# Schaltplan.net
KiCad netlist of a schematic drawn in EAGLE
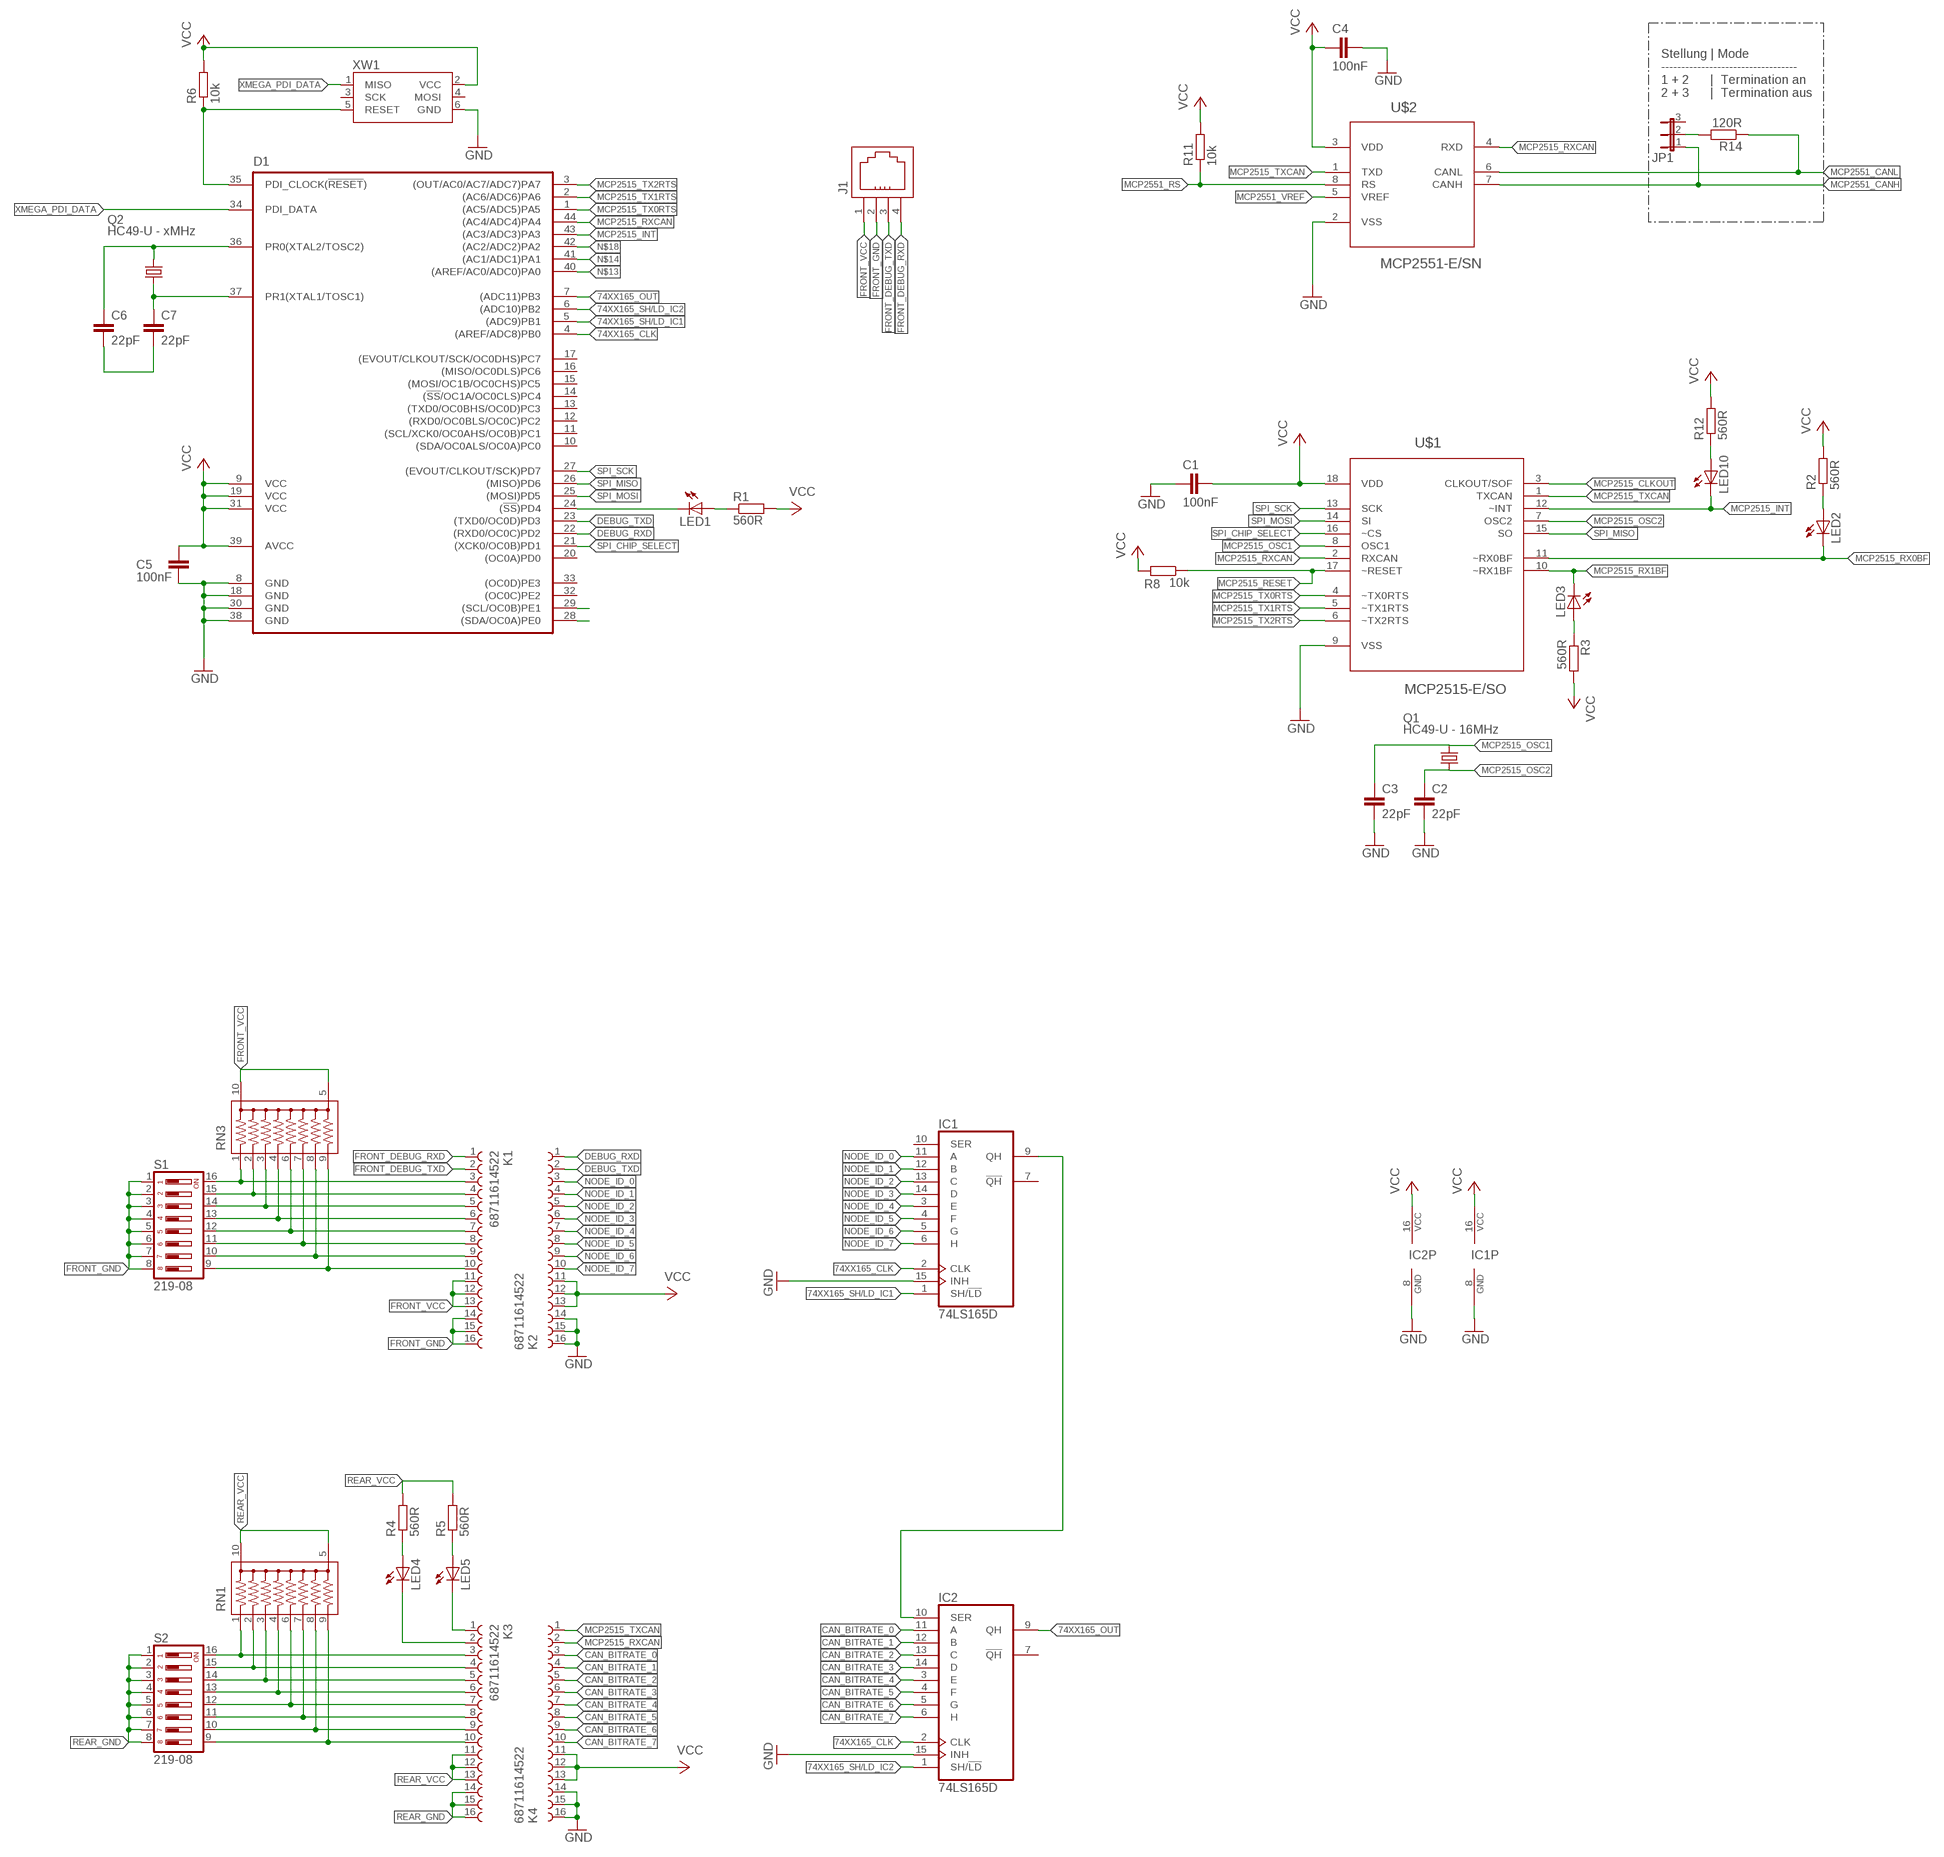
[diagram p0: schematic, sheet 1]

(export (version "E")
  (design (tool "Eeschema 10.0.6"))
  (components
    (comp (ref "C1")
      (value "100nF")
      (footprint "eagle-import:C1206")
      (libsource (lib "eagle-import") (part "C-EUC1206"))
    )
    (comp (ref "C2")
      (value "22pF")
      (footprint "eagle-import:C1206")
      (libsource (lib "eagle-import") (part "C-EUC1206"))
    )
    (comp (ref "C3")
      (value "22pF")
      (footprint "eagle-import:C1206")
      (libsource (lib "eagle-import") (part "C-EUC1206"))
    )
    (comp (ref "C4")
      (value "100nF")
      (footprint "eagle-import:C1206")
      (libsource (lib "eagle-import") (part "C-EUC1206"))
    )
    (comp (ref "C5")
      (value "100nF")
      (footprint "eagle-import:C1206")
      (libsource (lib "eagle-import") (part "C-EUC1206"))
    )
    (comp (ref "C6")
      (value "22pF")
      (footprint "eagle-import:C1206")
      (libsource (lib "eagle-import") (part "C-EUC1206"))
    )
    (comp (ref "C7")
      (value "22pF")
      (footprint "eagle-import:C1206")
      (libsource (lib "eagle-import") (part "C-EUC1206"))
    )
    (comp (ref "D1")
      (value "ATXMEGA16D4/32D4/64D4/128D4-A")
      (footprint "eagle-import:TQFP44A")
      (libsource (lib "eagle-import") (part "ATXMEGA16D4/32D4/64D4/128D4-A"))
    )
    (comp (ref "IC1")
      (value "74LS165D")
      (footprint "eagle-import:SO16")
      (libsource (lib "eagle-import") (part "74165DLS"))
    )
    (comp (ref "IC2")
      (value "74LS165D")
      (footprint "eagle-import:SO16")
      (libsource (lib "eagle-import") (part "74165DLS"))
    )
    (comp (ref "J1")
      (value "615004143821")
      (footprint "eagle-import:615004143821")
      (libsource (lib "eagle-import") (part "615004143821"))
    )
    (comp (ref "JP1")
      (value "JP2E")
      (footprint "eagle-import:JP2")
      (libsource (lib "eagle-import") (part "JP2E"))
    )
    (comp (ref "K1")
      (value "68711614522")
      (footprint "eagle-import:68711614522")
      (libsource (lib "eagle-import") (part "68711614522"))
    )
    (comp (ref "K2")
      (value "68711614522")
      (footprint "eagle-import:68711614522")
      (libsource (lib "eagle-import") (part "68711614522"))
    )
    (comp (ref "K3")
      (value "68711614522")
      (footprint "eagle-import:68711614522")
      (libsource (lib "eagle-import") (part "68711614522"))
    )
    (comp (ref "K4")
      (value "68711614522")
      (footprint "eagle-import:68711614522")
      (libsource (lib "eagle-import") (part "68711614522"))
    )
    (comp (ref "LED1")
      (value "LEDSML1206")
      (footprint "eagle-import:SML1206")
      (libsource (lib "eagle-import") (part "LEDSML1206"))
    )
    (comp (ref "LED2")
      (value "LEDSML1206")
      (footprint "eagle-import:SML1206")
      (libsource (lib "eagle-import") (part "LEDSML1206"))
    )
    (comp (ref "LED3")
      (value "LEDSML1206")
      (footprint "eagle-import:SML1206")
      (libsource (lib "eagle-import") (part "LEDSML1206"))
    )
    (comp (ref "LED4")
      (value "LEDSML1206")
      (footprint "eagle-import:SML1206")
      (libsource (lib "eagle-import") (part "LEDSML1206"))
    )
    (comp (ref "LED5")
      (value "LEDSML1206")
      (footprint "eagle-import:SML1206")
      (libsource (lib "eagle-import") (part "LEDSML1206"))
    )
    (comp (ref "LED10")
      (value "LEDSML1206")
      (footprint "eagle-import:SML1206")
      (libsource (lib "eagle-import") (part "LEDSML1206"))
    )
    (comp (ref "Q1")
      (value "HC49-U - 16MHz")
      (footprint "eagle-import:HC49")
      (libsource (lib "eagle-import") (part "HC49-U"))
    )
    (comp (ref "Q2")
      (value "HC49-U - xMHz")
      (footprint "eagle-import:HC49")
      (libsource (lib "eagle-import") (part "HC49-U"))
    )
    (comp (ref "R1")
      (value "560R")
      (footprint "eagle-import:R1206")
      (libsource (lib "eagle-import") (part "R-EU_R1206"))
    )
    (comp (ref "R2")
      (value "560R")
      (footprint "eagle-import:R1206")
      (libsource (lib "eagle-import") (part "R-EU_R1206"))
    )
    (comp (ref "R3")
      (value "560R")
      (footprint "eagle-import:R1206")
      (libsource (lib "eagle-import") (part "R-EU_R1206"))
    )
    (comp (ref "R4")
      (value "560R")
      (footprint "eagle-import:R1206")
      (libsource (lib "eagle-import") (part "R-EU_R1206"))
    )
    (comp (ref "R5")
      (value "560R")
      (footprint "eagle-import:R1206")
      (libsource (lib "eagle-import") (part "R-EU_R1206"))
    )
    (comp (ref "R6")
      (value "10k")
      (footprint "eagle-import:R1206")
      (libsource (lib "eagle-import") (part "R-EU_R1206"))
    )
    (comp (ref "R8")
      (value "10k")
      (footprint "eagle-import:R1206")
      (libsource (lib "eagle-import") (part "R-EU_R1206"))
    )
    (comp (ref "R11")
      (value "10k")
      (footprint "eagle-import:R1206")
      (libsource (lib "eagle-import") (part "R-EU_R1206"))
    )
    (comp (ref "R12")
      (value "560R")
      (footprint "eagle-import:R1206")
      (libsource (lib "eagle-import") (part "R-EU_R1206"))
    )
    (comp (ref "R14")
      (value "120R")
      (footprint "eagle-import:R1206")
      (libsource (lib "eagle-import") (part "R-EU_R1206"))
    )
    (comp (ref "RN1")
      (value "745-10")
      (footprint "eagle-import:745-10")
      (libsource (lib "eagle-import") (part "745-10"))
    )
    (comp (ref "RN3")
      (value "745-10")
      (footprint "eagle-import:745-10")
      (libsource (lib "eagle-import") (part "745-10"))
    )
    (comp (ref "S1")
      (value "219-08")
      (footprint "eagle-import:CTS-219-08")
      (libsource (lib "eagle-import") (part "219-08"))
    )
    (comp (ref "S2")
      (value "219-08")
      (footprint "eagle-import:CTS-219-08")
      (libsource (lib "eagle-import") (part "219-08"))
    )
    (comp (ref "U$1")
      (value "MCP2515-E/SO")
      (footprint "eagle-import:SOIC127P1030X265-18N")
      (libsource (lib "eagle-import") (part "MCP2515-E/SO"))
    )
    (comp (ref "U$2")
      (value "MCP2551-E/SN")
      (footprint "eagle-import:SOIC127P600X175-8N")
      (libsource (lib "eagle-import") (part "MCP2551-E/SN"))
    )
    (comp (ref "XW1")
      (value "WSL6")
      (footprint "eagle-import:WSL")
      (libsource (lib "eagle-import") (part "WSL6"))
    )
  )
  (nets
    (net (code "1") (name "74XX165_CLK") (class "Default")
      (node (ref "D1") (pin "4") (pinfunction "(AREF/ADC8)PB0_4") (pintype "bidirectional"))
      (node (ref "IC1") (pin "2") (pinfunction "CLK_2") (pintype "input"))
      (node (ref "IC2") (pin "2") (pinfunction "CLK_2") (pintype "input"))
    )
    (net (code "2") (name "74XX165_OUT") (class "Default")
      (node (ref "D1") (pin "7") (pinfunction "(ADC11)PB3_7") (pintype "bidirectional"))
      (node (ref "IC2") (pin "9") (pinfunction "QH_9") (pintype "output"))
    )
    (net (code "3") (name "74XX165_SH{slash}LD_IC1") (class "Default")
      (node (ref "D1") (pin "5") (pinfunction "(ADC9)PB1_5") (pintype "bidirectional"))
      (node (ref "IC1") (pin "1") (pinfunction "SH/~{LD}_1") (pintype "input"))
    )
    (net (code "4") (name "74XX165_SH{slash}LD_IC2") (class "Default")
      (node (ref "D1") (pin "6") (pinfunction "(ADC10)PB2_6") (pintype "bidirectional"))
      (node (ref "IC2") (pin "1") (pinfunction "SH/~{LD}_1") (pintype "input"))
    )
    (net (code "5") (name "CAN_BITRATE_0") (class "Default")
      (node (ref "IC2") (pin "11") (pinfunction "A_11") (pintype "input"))
      (node (ref "K4") (pin "3") (pinfunction "3_3") (pintype "passive"))
    )
    (net (code "6") (name "CAN_BITRATE_1") (class "Default")
      (node (ref "IC2") (pin "12") (pinfunction "B_12") (pintype "input"))
      (node (ref "K4") (pin "4") (pinfunction "4_4") (pintype "passive"))
    )
    (net (code "7") (name "CAN_BITRATE_2") (class "Default")
      (node (ref "IC2") (pin "13") (pinfunction "C_13") (pintype "input"))
      (node (ref "K4") (pin "5") (pinfunction "5_5") (pintype "passive"))
    )
    (net (code "8") (name "CAN_BITRATE_3") (class "Default")
      (node (ref "IC2") (pin "14") (pinfunction "D_14") (pintype "input"))
      (node (ref "K4") (pin "6") (pinfunction "6_6") (pintype "passive"))
    )
    (net (code "9") (name "CAN_BITRATE_4") (class "Default")
      (node (ref "IC2") (pin "3") (pinfunction "E_3") (pintype "input"))
      (node (ref "K4") (pin "7") (pinfunction "7_7") (pintype "passive"))
    )
    (net (code "10") (name "CAN_BITRATE_5") (class "Default")
      (node (ref "IC2") (pin "4") (pinfunction "F_4") (pintype "input"))
      (node (ref "K4") (pin "8") (pinfunction "8_8") (pintype "passive"))
    )
    (net (code "11") (name "CAN_BITRATE_6") (class "Default")
      (node (ref "IC2") (pin "5") (pinfunction "G_5") (pintype "input"))
      (node (ref "K4") (pin "9") (pinfunction "9_9") (pintype "passive"))
    )
    (net (code "12") (name "CAN_BITRATE_7") (class "Default")
      (node (ref "IC2") (pin "6") (pinfunction "H_6") (pintype "input"))
      (node (ref "K4") (pin "10") (pinfunction "10_10") (pintype "passive"))
    )
    (net (code "13") (name "DEBUG_RXD") (class "Default")
      (node (ref "D1") (pin "22") (pinfunction "(RXD0/OC0C)PD2_22") (pintype "bidirectional"))
      (node (ref "K2") (pin "1") (pinfunction "1_1") (pintype "passive"))
    )
    (net (code "14") (name "DEBUG_TXD") (class "Default")
      (node (ref "D1") (pin "23") (pinfunction "(TXD0/OC0D)PD3_23") (pintype "bidirectional"))
      (node (ref "K2") (pin "2") (pinfunction "2_2") (pintype "passive"))
    )
    (net (code "15") (name "FRONT_DEBUG_RXD") (class "Default")
      (node (ref "J1") (pin "4") (pinfunction "1_4") (pintype "passive"))
      (node (ref "K1") (pin "1") (pinfunction "1_1") (pintype "passive"))
    )
    (net (code "16") (name "FRONT_DEBUG_TXD") (class "Default")
      (node (ref "J1") (pin "3") (pinfunction "2_3") (pintype "passive"))
      (node (ref "K1") (pin "2") (pinfunction "2_2") (pintype "passive"))
    )
    (net (code "17") (name "FRONT_GND") (class "Default")
      (node (ref "J1") (pin "2") (pinfunction "3_2") (pintype "passive"))
      (node (ref "K1") (pin "14") (pinfunction "14_14") (pintype "passive"))
      (node (ref "K1") (pin "15") (pinfunction "15_15") (pintype "passive"))
      (node (ref "K1") (pin "16") (pinfunction "16_16") (pintype "passive"))
      (node (ref "S1") (pin "1") (pinfunction "1_1") (pintype "passive"))
      (node (ref "S1") (pin "2") (pinfunction "2_2") (pintype "passive"))
      (node (ref "S1") (pin "3") (pinfunction "3_3") (pintype "passive"))
      (node (ref "S1") (pin "4") (pinfunction "4_4") (pintype "passive"))
      (node (ref "S1") (pin "5") (pinfunction "5_5") (pintype "passive"))
      (node (ref "S1") (pin "6") (pinfunction "6_6") (pintype "passive"))
      (node (ref "S1") (pin "7") (pinfunction "7_7") (pintype "passive"))
      (node (ref "S1") (pin "8") (pinfunction "8_8") (pintype "passive"))
    )
    (net (code "18") (name "FRONT_VCC") (class "Default")
      (node (ref "J1") (pin "1") (pinfunction "4_1") (pintype "passive"))
      (node (ref "K1") (pin "11") (pinfunction "11_11") (pintype "passive"))
      (node (ref "K1") (pin "12") (pinfunction "12_12") (pintype "passive"))
      (node (ref "K1") (pin "13") (pinfunction "13_13") (pintype "passive"))
      (node (ref "RN3") (pin "10") (pinfunction "10_10") (pintype "passive"))
      (node (ref "RN3") (pin "5") (pinfunction "5_5") (pintype "passive"))
    )
    (net (code "19") (name "GND") (class "Default")
      (node (ref "C1") (pin "2") (pinfunction "2_2") (pintype "passive"))
      (node (ref "C2") (pin "2") (pinfunction "2_2") (pintype "passive"))
      (node (ref "C3") (pin "2") (pinfunction "2_2") (pintype "passive"))
      (node (ref "C4") (pin "1") (pinfunction "1_1") (pintype "passive"))
      (node (ref "C5") (pin "2") (pinfunction "2_2") (pintype "passive"))
      (node (ref "D1") (pin "18") (pinfunction "GND_18") (pintype "power_in"))
      (node (ref "D1") (pin "30") (pinfunction "GND_30") (pintype "power_in"))
      (node (ref "D1") (pin "38") (pinfunction "GND_38") (pintype "power_in"))
      (node (ref "D1") (pin "8") (pinfunction "GND_8") (pintype "power_in"))
      (node (ref "IC1") (pin "15") (pinfunction "INH_15") (pintype "input"))
      (node (ref "IC1") (pin "8") (pinfunction "GND_8") (pintype "power_in"))
      (node (ref "IC2") (pin "15") (pinfunction "INH_15") (pintype "input"))
      (node (ref "IC2") (pin "8") (pinfunction "GND_8") (pintype "power_in"))
      (node (ref "K2") (pin "14") (pinfunction "14_14") (pintype "passive"))
      (node (ref "K2") (pin "15") (pinfunction "15_15") (pintype "passive"))
      (node (ref "K2") (pin "16") (pinfunction "16_16") (pintype "passive"))
      (node (ref "K4") (pin "14") (pinfunction "14_14") (pintype "passive"))
      (node (ref "K4") (pin "15") (pinfunction "15_15") (pintype "passive"))
      (node (ref "K4") (pin "16") (pinfunction "16_16") (pintype "passive"))
      (node (ref "U$1") (pin "9") (pinfunction "VSS_9") (pintype "power_in"))
      (node (ref "U$2") (pin "2") (pinfunction "VSS_2") (pintype "power_in"))
      (node (ref "XW1") (pin "6") (pinfunction "GND_6") (pintype "power_in"))
    )
    (net (code "20") (name "MCP2515_CLKOUT") (class "Default")
      (node (ref "U$1") (pin "3") (pinfunction "CLKOUT/SOF_3") (pintype "output"))
    )
    (net (code "21") (name "MCP2515_INT") (class "Default")
      (node (ref "D1") (pin "43") (pinfunction "(AC3/ADC3)PA3_43") (pintype "bidirectional"))
      (node (ref "LED10") (pin "C") (pinfunction "C_C") (pintype "passive"))
      (node (ref "U$1") (pin "12") (pinfunction "~{INT}_12") (pintype "output"))
    )
    (net (code "22") (name "MCP2515_OSC1") (class "Default")
      (node (ref "C3") (pin "1") (pinfunction "1_1") (pintype "passive"))
      (node (ref "Q1") (pin "2") (pinfunction "2_2") (pintype "passive"))
      (node (ref "U$1") (pin "8") (pinfunction "OSC1_8") (pintype "input"))
    )
    (net (code "23") (name "MCP2515_OSC2") (class "Default")
      (node (ref "C2") (pin "1") (pinfunction "1_1") (pintype "passive"))
      (node (ref "Q1") (pin "1") (pinfunction "1_1") (pintype "passive"))
      (node (ref "U$1") (pin "7") (pinfunction "OSC2_7") (pintype "output"))
    )
    (net (code "24") (name "MCP2515_RESET") (class "Default")
      (node (ref "R8") (pin "1") (pinfunction "1_1") (pintype "passive"))
      (node (ref "U$1") (pin "17") (pinfunction "~{RESET}_17") (pintype "input"))
    )
    (net (code "25") (name "MCP2515_RX0BF") (class "Default")
      (node (ref "LED2") (pin "C") (pinfunction "C_C") (pintype "passive"))
      (node (ref "U$1") (pin "11") (pinfunction "~{RX0BF}_11") (pintype "output"))
    )
    (net (code "26") (name "MCP2515_RX1BF") (class "Default")
      (node (ref "LED3") (pin "C") (pinfunction "C_C") (pintype "passive"))
      (node (ref "U$1") (pin "10") (pinfunction "~{RX1BF}_10") (pintype "output"))
    )
    (net (code "27") (name "MCP2515_RXCAN") (class "Default")
      (node (ref "D1") (pin "44") (pinfunction "(AC4/ADC4)PA4_44") (pintype "bidirectional"))
      (node (ref "K4") (pin "2") (pinfunction "2_2") (pintype "passive"))
      (node (ref "U$1") (pin "2") (pinfunction "RXCAN_2") (pintype "input"))
      (node (ref "U$2") (pin "4") (pinfunction "RXD_4") (pintype "output"))
    )
    (net (code "28") (name "MCP2515_TX0RTS") (class "Default")
      (node (ref "D1") (pin "1") (pinfunction "(AC5/ADC5)PA5_1") (pintype "bidirectional"))
      (node (ref "U$1") (pin "4") (pinfunction "~{TX0RTS}_4") (pintype "input"))
    )
    (net (code "29") (name "MCP2515_TX1RTS") (class "Default")
      (node (ref "D1") (pin "2") (pinfunction "(AC6/ADC6)PA6_2") (pintype "bidirectional"))
      (node (ref "U$1") (pin "5") (pinfunction "~{TX1RTS}_5") (pintype "input"))
    )
    (net (code "30") (name "MCP2515_TX2RTS") (class "Default")
      (node (ref "D1") (pin "3") (pinfunction "(OUT/AC0/AC7/ADC7)PA7_3") (pintype "bidirectional"))
      (node (ref "U$1") (pin "6") (pinfunction "~{TX2RTS}_6") (pintype "input"))
    )
    (net (code "31") (name "MCP2515_TXCAN") (class "Default")
      (node (ref "K4") (pin "1") (pinfunction "1_1") (pintype "passive"))
      (node (ref "U$1") (pin "1") (pinfunction "TXCAN_1") (pintype "output"))
      (node (ref "U$2") (pin "1") (pinfunction "TXD_1") (pintype "input"))
    )
    (net (code "32") (name "MCP2551_CANH") (class "Default")
      (node (ref "JP1") (pin "1") (pinfunction "1_1") (pintype "passive"))
      (node (ref "U$2") (pin "7") (pinfunction "CANH_7") (pintype "output"))
    )
    (net (code "33") (name "MCP2551_CANL") (class "Default")
      (node (ref "R14") (pin "1") (pinfunction "1_1") (pintype "passive"))
      (node (ref "U$2") (pin "6") (pinfunction "CANL_6") (pintype "output"))
    )
    (net (code "34") (name "MCP2551_RS") (class "Default")
      (node (ref "R11") (pin "1") (pinfunction "1_1") (pintype "passive"))
      (node (ref "U$2") (pin "8") (pinfunction "RS_8") (pintype "input"))
    )
    (net (code "35") (name "MCP2551_VREF") (class "Default")
      (node (ref "U$2") (pin "5") (pinfunction "VREF_5") (pintype "input"))
    )
    (net (code "36") (name "N$13") (class "Default")
      (node (ref "D1") (pin "40") (pinfunction "(AREF/AC0/ADC0)PA0_40") (pintype "bidirectional"))
    )
    (net (code "37") (name "N$14") (class "Default")
      (node (ref "D1") (pin "41") (pinfunction "(AC1/ADC1)PA1_41") (pintype "bidirectional"))
    )
    (net (code "38") (name "N$18") (class "Default")
      (node (ref "D1") (pin "42") (pinfunction "(AC2/ADC2)PA2_42") (pintype "bidirectional"))
    )
    (net (code "39") (name "NODE_ID_0") (class "Default")
      (node (ref "IC1") (pin "11") (pinfunction "A_11") (pintype "input"))
      (node (ref "K2") (pin "3") (pinfunction "3_3") (pintype "passive"))
    )
    (net (code "40") (name "NODE_ID_1") (class "Default")
      (node (ref "IC1") (pin "12") (pinfunction "B_12") (pintype "input"))
      (node (ref "K2") (pin "4") (pinfunction "4_4") (pintype "passive"))
    )
    (net (code "41") (name "NODE_ID_2") (class "Default")
      (node (ref "IC1") (pin "13") (pinfunction "C_13") (pintype "input"))
      (node (ref "K2") (pin "5") (pinfunction "5_5") (pintype "passive"))
    )
    (net (code "42") (name "NODE_ID_3") (class "Default")
      (node (ref "IC1") (pin "14") (pinfunction "D_14") (pintype "input"))
      (node (ref "K2") (pin "6") (pinfunction "6_6") (pintype "passive"))
    )
    (net (code "43") (name "NODE_ID_4") (class "Default")
      (node (ref "IC1") (pin "3") (pinfunction "E_3") (pintype "input"))
      (node (ref "K2") (pin "7") (pinfunction "7_7") (pintype "passive"))
    )
    (net (code "44") (name "NODE_ID_5") (class "Default")
      (node (ref "IC1") (pin "4") (pinfunction "F_4") (pintype "input"))
      (node (ref "K2") (pin "8") (pinfunction "8_8") (pintype "passive"))
    )
    (net (code "45") (name "NODE_ID_6") (class "Default")
      (node (ref "IC1") (pin "5") (pinfunction "G_5") (pintype "input"))
      (node (ref "K2") (pin "9") (pinfunction "9_9") (pintype "passive"))
    )
    (net (code "46") (name "NODE_ID_7") (class "Default")
      (node (ref "IC1") (pin "6") (pinfunction "H_6") (pintype "input"))
      (node (ref "K2") (pin "10") (pinfunction "10_10") (pintype "passive"))
    )
    (net (code "47") (name "Net-(C6-Pad2)") (class "Default")
      (node (ref "C6") (pin "2") (pinfunction "2_2") (pintype "passive"))
      (node (ref "C7") (pin "2") (pinfunction "2_2") (pintype "passive"))
    )
    (net (code "48") (name "Net-(D1-(~{SS})PD4)") (class "Default")
      (node (ref "D1") (pin "24") (pinfunction "(~{SS})PD4_24") (pintype "bidirectional"))
      (node (ref "LED1") (pin "C") (pinfunction "C_C") (pintype "passive"))
    )
    (net (code "49") (name "Net-(D1-PDI_CLOCK(~{RESET}))") (class "Default")
      (node (ref "D1") (pin "35") (pinfunction "PDI_CLOCK(~{RESET})_35") (pintype "input"))
      (node (ref "R6") (pin "1") (pinfunction "1_1") (pintype "passive"))
      (node (ref "XW1") (pin "5") (pinfunction "RESET_5") (pintype "bidirectional"))
    )
    (net (code "50") (name "Net-(D1-PR0(XTAL2{slash}TOSC2))") (class "Default")
      (node (ref "C6") (pin "1") (pinfunction "1_1") (pintype "passive"))
      (node (ref "D1") (pin "36") (pinfunction "PR0(XTAL2/TOSC2)_36") (pintype "bidirectional"))
      (node (ref "Q2") (pin "2") (pinfunction "2_2") (pintype "passive"))
    )
    (net (code "51") (name "Net-(D1-PR1(XTAL1{slash}TOSC1))") (class "Default")
      (node (ref "C7") (pin "1") (pinfunction "1_1") (pintype "passive"))
      (node (ref "D1") (pin "37") (pinfunction "PR1(XTAL1/TOSC1)_37") (pintype "bidirectional"))
      (node (ref "Q2") (pin "1") (pinfunction "1_1") (pintype "passive"))
    )
    (net (code "52") (name "Net-(IC1A-QH)") (class "Default")
      (node (ref "IC1") (pin "9") (pinfunction "QH_9") (pintype "output"))
      (node (ref "IC2") (pin "10") (pinfunction "SER_10") (pintype "input"))
    )
    (net (code "53") (name "Net-(JP1-Pad2)") (class "Default")
      (node (ref "JP1") (pin "2") (pinfunction "2_2") (pintype "passive"))
      (node (ref "R14") (pin "2") (pinfunction "2_2") (pintype "passive"))
    )
    (net (code "54") (name "Net-(K1-Pad3)") (class "Default")
      (node (ref "K1") (pin "3") (pinfunction "3_3") (pintype "passive"))
      (node (ref "RN3") (pin "1") (pinfunction "1_1") (pintype "passive"))
      (node (ref "S1") (pin "16") (pinfunction "16_16") (pintype "passive"))
    )
    (net (code "55") (name "Net-(K1-Pad4)") (class "Default")
      (node (ref "K1") (pin "4") (pinfunction "4_4") (pintype "passive"))
      (node (ref "RN3") (pin "2") (pinfunction "2_2") (pintype "passive"))
      (node (ref "S1") (pin "15") (pinfunction "15_15") (pintype "passive"))
    )
    (net (code "56") (name "Net-(K1-Pad5)") (class "Default")
      (node (ref "K1") (pin "5") (pinfunction "5_5") (pintype "passive"))
      (node (ref "RN3") (pin "3") (pinfunction "3_3") (pintype "passive"))
      (node (ref "S1") (pin "14") (pinfunction "14_14") (pintype "passive"))
    )
    (net (code "57") (name "Net-(K1-Pad6)") (class "Default")
      (node (ref "K1") (pin "6") (pinfunction "6_6") (pintype "passive"))
      (node (ref "RN3") (pin "4") (pinfunction "4_4") (pintype "passive"))
      (node (ref "S1") (pin "13") (pinfunction "13_13") (pintype "passive"))
    )
    (net (code "58") (name "Net-(K1-Pad7)") (class "Default")
      (node (ref "K1") (pin "7") (pinfunction "7_7") (pintype "passive"))
      (node (ref "RN3") (pin "6") (pinfunction "6_6") (pintype "passive"))
      (node (ref "S1") (pin "12") (pinfunction "12_12") (pintype "passive"))
    )
    (net (code "59") (name "Net-(K1-Pad8)") (class "Default")
      (node (ref "K1") (pin "8") (pinfunction "8_8") (pintype "passive"))
      (node (ref "RN3") (pin "7") (pinfunction "7_7") (pintype "passive"))
      (node (ref "S1") (pin "11") (pinfunction "11_11") (pintype "passive"))
    )
    (net (code "60") (name "Net-(K1-Pad9)") (class "Default")
      (node (ref "K1") (pin "9") (pinfunction "9_9") (pintype "passive"))
      (node (ref "RN3") (pin "8") (pinfunction "8_8") (pintype "passive"))
      (node (ref "S1") (pin "10") (pinfunction "10_10") (pintype "passive"))
    )
    (net (code "61") (name "Net-(K1-Pad10)") (class "Default")
      (node (ref "K1") (pin "10") (pinfunction "10_10") (pintype "passive"))
      (node (ref "RN3") (pin "9") (pinfunction "9_9") (pintype "passive"))
      (node (ref "S1") (pin "9") (pinfunction "9_9") (pintype "passive"))
    )
    (net (code "62") (name "Net-(K3-Pad1)") (class "Default")
      (node (ref "K3") (pin "1") (pinfunction "1_1") (pintype "passive"))
      (node (ref "LED5") (pin "C") (pinfunction "C_C") (pintype "passive"))
    )
    (net (code "63") (name "Net-(K3-Pad2)") (class "Default")
      (node (ref "K3") (pin "2") (pinfunction "2_2") (pintype "passive"))
      (node (ref "LED4") (pin "C") (pinfunction "C_C") (pintype "passive"))
    )
    (net (code "64") (name "Net-(K3-Pad3)") (class "Default")
      (node (ref "K3") (pin "3") (pinfunction "3_3") (pintype "passive"))
      (node (ref "RN1") (pin "1") (pinfunction "1_1") (pintype "passive"))
      (node (ref "S2") (pin "16") (pinfunction "16_16") (pintype "passive"))
    )
    (net (code "65") (name "Net-(K3-Pad4)") (class "Default")
      (node (ref "K3") (pin "4") (pinfunction "4_4") (pintype "passive"))
      (node (ref "RN1") (pin "2") (pinfunction "2_2") (pintype "passive"))
      (node (ref "S2") (pin "15") (pinfunction "15_15") (pintype "passive"))
    )
    (net (code "66") (name "Net-(K3-Pad5)") (class "Default")
      (node (ref "K3") (pin "5") (pinfunction "5_5") (pintype "passive"))
      (node (ref "RN1") (pin "3") (pinfunction "3_3") (pintype "passive"))
      (node (ref "S2") (pin "14") (pinfunction "14_14") (pintype "passive"))
    )
    (net (code "67") (name "Net-(K3-Pad6)") (class "Default")
      (node (ref "K3") (pin "6") (pinfunction "6_6") (pintype "passive"))
      (node (ref "RN1") (pin "4") (pinfunction "4_4") (pintype "passive"))
      (node (ref "S2") (pin "13") (pinfunction "13_13") (pintype "passive"))
    )
    (net (code "68") (name "Net-(K3-Pad7)") (class "Default")
      (node (ref "K3") (pin "7") (pinfunction "7_7") (pintype "passive"))
      (node (ref "RN1") (pin "6") (pinfunction "6_6") (pintype "passive"))
      (node (ref "S2") (pin "12") (pinfunction "12_12") (pintype "passive"))
    )
    (net (code "69") (name "Net-(K3-Pad8)") (class "Default")
      (node (ref "K3") (pin "8") (pinfunction "8_8") (pintype "passive"))
      (node (ref "RN1") (pin "7") (pinfunction "7_7") (pintype "passive"))
      (node (ref "S2") (pin "11") (pinfunction "11_11") (pintype "passive"))
    )
    (net (code "70") (name "Net-(K3-Pad9)") (class "Default")
      (node (ref "K3") (pin "9") (pinfunction "9_9") (pintype "passive"))
      (node (ref "RN1") (pin "8") (pinfunction "8_8") (pintype "passive"))
      (node (ref "S2") (pin "10") (pinfunction "10_10") (pintype "passive"))
    )
    (net (code "71") (name "Net-(K3-Pad10)") (class "Default")
      (node (ref "K3") (pin "10") (pinfunction "10_10") (pintype "passive"))
      (node (ref "RN1") (pin "9") (pinfunction "9_9") (pintype "passive"))
      (node (ref "S2") (pin "9") (pinfunction "9_9") (pintype "passive"))
    )
    (net (code "72") (name "Net-(LED1-PadA)") (class "Default")
      (node (ref "LED1") (pin "A") (pinfunction "A_A") (pintype "passive"))
      (node (ref "R1") (pin "1") (pinfunction "1_1") (pintype "passive"))
    )
    (net (code "73") (name "Net-(LED2-PadA)") (class "Default")
      (node (ref "LED2") (pin "A") (pinfunction "A_A") (pintype "passive"))
      (node (ref "R2") (pin "1") (pinfunction "1_1") (pintype "passive"))
    )
    (net (code "74") (name "Net-(LED3-PadA)") (class "Default")
      (node (ref "LED3") (pin "A") (pinfunction "A_A") (pintype "passive"))
      (node (ref "R3") (pin "1") (pinfunction "1_1") (pintype "passive"))
    )
    (net (code "75") (name "Net-(LED4-PadA)") (class "Default")
      (node (ref "LED4") (pin "A") (pinfunction "A_A") (pintype "passive"))
      (node (ref "R4") (pin "1") (pinfunction "1_1") (pintype "passive"))
    )
    (net (code "76") (name "Net-(LED5-PadA)") (class "Default")
      (node (ref "LED5") (pin "A") (pinfunction "A_A") (pintype "passive"))
      (node (ref "R5") (pin "1") (pinfunction "1_1") (pintype "passive"))
    )
    (net (code "77") (name "Net-(LED10-PadA)") (class "Default")
      (node (ref "LED10") (pin "A") (pinfunction "A_A") (pintype "passive"))
      (node (ref "R12") (pin "1") (pinfunction "1_1") (pintype "passive"))
    )
    (net (code "78") (name "REAR_GND") (class "Default")
      (node (ref "K3") (pin "14") (pinfunction "14_14") (pintype "passive"))
      (node (ref "K3") (pin "15") (pinfunction "15_15") (pintype "passive"))
      (node (ref "K3") (pin "16") (pinfunction "16_16") (pintype "passive"))
      (node (ref "S2") (pin "1") (pinfunction "1_1") (pintype "passive"))
      (node (ref "S2") (pin "2") (pinfunction "2_2") (pintype "passive"))
      (node (ref "S2") (pin "3") (pinfunction "3_3") (pintype "passive"))
      (node (ref "S2") (pin "4") (pinfunction "4_4") (pintype "passive"))
      (node (ref "S2") (pin "5") (pinfunction "5_5") (pintype "passive"))
      (node (ref "S2") (pin "6") (pinfunction "6_6") (pintype "passive"))
      (node (ref "S2") (pin "7") (pinfunction "7_7") (pintype "passive"))
      (node (ref "S2") (pin "8") (pinfunction "8_8") (pintype "passive"))
    )
    (net (code "79") (name "REAR_VCC") (class "Default")
      (node (ref "K3") (pin "11") (pinfunction "11_11") (pintype "passive"))
      (node (ref "K3") (pin "12") (pinfunction "12_12") (pintype "passive"))
      (node (ref "K3") (pin "13") (pinfunction "13_13") (pintype "passive"))
      (node (ref "R4") (pin "2") (pinfunction "2_2") (pintype "passive"))
      (node (ref "R5") (pin "2") (pinfunction "2_2") (pintype "passive"))
      (node (ref "RN1") (pin "10") (pinfunction "10_10") (pintype "passive"))
      (node (ref "RN1") (pin "5") (pinfunction "5_5") (pintype "passive"))
    )
    (net (code "80") (name "SPI_CHIP_SELECT") (class "Default")
      (node (ref "D1") (pin "21") (pinfunction "(XCK0/OC0B)PD1_21") (pintype "bidirectional"))
      (node (ref "U$1") (pin "16") (pinfunction "~{CS}_16") (pintype "input"))
    )
    (net (code "81") (name "SPI_MISO") (class "Default")
      (node (ref "D1") (pin "26") (pinfunction "(MISO)PD6_26") (pintype "bidirectional"))
      (node (ref "U$1") (pin "15") (pinfunction "SO_15") (pintype "output"))
    )
    (net (code "82") (name "SPI_MOSI") (class "Default")
      (node (ref "D1") (pin "25") (pinfunction "(MOSI)PD5_25") (pintype "bidirectional"))
      (node (ref "U$1") (pin "14") (pinfunction "SI_14") (pintype "input"))
    )
    (net (code "83") (name "SPI_SCK") (class "Default")
      (node (ref "D1") (pin "27") (pinfunction "(EVOUT/CLKOUT/SCK)PD7_27") (pintype "bidirectional"))
      (node (ref "U$1") (pin "13") (pinfunction "SCK_13") (pintype "input"))
    )
    (net (code "84") (name "VCC") (class "Default")
      (node (ref "C1") (pin "1") (pinfunction "1_1") (pintype "passive"))
      (node (ref "C4") (pin "2") (pinfunction "2_2") (pintype "passive"))
      (node (ref "C5") (pin "1") (pinfunction "1_1") (pintype "passive"))
      (node (ref "D1") (pin "19") (pinfunction "VCC_19") (pintype "power_in"))
      (node (ref "D1") (pin "31") (pinfunction "VCC_31") (pintype "power_in"))
      (node (ref "D1") (pin "39") (pinfunction "AVCC_39") (pintype "power_in"))
      (node (ref "D1") (pin "9") (pinfunction "VCC_9") (pintype "power_in"))
      (node (ref "IC1") (pin "16") (pinfunction "VCC_16") (pintype "power_in"))
      (node (ref "IC2") (pin "16") (pinfunction "VCC_16") (pintype "power_in"))
      (node (ref "K2") (pin "11") (pinfunction "11_11") (pintype "passive"))
      (node (ref "K2") (pin "12") (pinfunction "12_12") (pintype "passive"))
      (node (ref "K2") (pin "13") (pinfunction "13_13") (pintype "passive"))
      (node (ref "K4") (pin "11") (pinfunction "11_11") (pintype "passive"))
      (node (ref "K4") (pin "12") (pinfunction "12_12") (pintype "passive"))
      (node (ref "K4") (pin "13") (pinfunction "13_13") (pintype "passive"))
      (node (ref "R1") (pin "2") (pinfunction "2_2") (pintype "passive"))
      (node (ref "R11") (pin "2") (pinfunction "2_2") (pintype "passive"))
      (node (ref "R12") (pin "2") (pinfunction "2_2") (pintype "passive"))
      (node (ref "R2") (pin "2") (pinfunction "2_2") (pintype "passive"))
      (node (ref "R3") (pin "2") (pinfunction "2_2") (pintype "passive"))
      (node (ref "R6") (pin "2") (pinfunction "2_2") (pintype "passive"))
      (node (ref "R8") (pin "2") (pinfunction "2_2") (pintype "passive"))
      (node (ref "U$1") (pin "18") (pinfunction "VDD_18") (pintype "power_in"))
      (node (ref "U$2") (pin "3") (pinfunction "VDD_3") (pintype "power_in"))
      (node (ref "XW1") (pin "2") (pinfunction "VCC_2") (pintype "power_in"))
    )
    (net (code "85") (name "XMEGA_PDI_DATA") (class "Default")
      (node (ref "D1") (pin "34") (pinfunction "PDI_DATA_34") (pintype "bidirectional"))
      (node (ref "XW1") (pin "1") (pinfunction "MISO_1") (pintype "bidirectional"))
    )
    (net (code "86") (name "unconnected-(D1-(EVOUT{slash}CLKOUT{slash}SCK{slash}OC0DHS)PC7-Pad17)") (class "Default")
      (node (ref "D1") (pin "17") (pinfunction "(EVOUT/CLKOUT/SCK/OC0DHS)PC7_17") (pintype "bidirectional"))
    )
    (net (code "87") (name "unconnected-(D1-(MISO{slash}OC0DLS)PC6-Pad16)") (class "Default")
      (node (ref "D1") (pin "16") (pinfunction "(MISO/OC0DLS)PC6_16") (pintype "bidirectional"))
    )
    (net (code "88") (name "unconnected-(D1-(MOSI{slash}OC1B{slash}OC0CHS)PC5-Pad15)") (class "Default")
      (node (ref "D1") (pin "15") (pinfunction "(MOSI/OC1B/OC0CHS)PC5_15") (pintype "bidirectional"))
    )
    (net (code "89") (name "unconnected-(D1-(OC0A)PD0-Pad20)") (class "Default")
      (node (ref "D1") (pin "20") (pinfunction "(OC0A)PD0_20") (pintype "bidirectional"))
    )
    (net (code "90") (name "unconnected-(D1-(OC0C)PE2-Pad32)") (class "Default")
      (node (ref "D1") (pin "32") (pinfunction "(OC0C)PE2_32") (pintype "bidirectional"))
    )
    (net (code "91") (name "unconnected-(D1-(OC0D)PE3-Pad33)") (class "Default")
      (node (ref "D1") (pin "33") (pinfunction "(OC0D)PE3_33") (pintype "bidirectional"))
    )
    (net (code "92") (name "unconnected-(D1-(RXD0{slash}OC0BLS{slash}OC0C)PC2-Pad12)") (class "Default")
      (node (ref "D1") (pin "12") (pinfunction "(RXD0/OC0BLS/OC0C)PC2_12") (pintype "bidirectional"))
    )
    (net (code "93") (name "unconnected-(D1-(SCL{slash}OC0B)PE1-Pad29)") (class "Default")
      (node (ref "D1") (pin "29") (pinfunction "(SCL/OC0B)PE1_29") (pintype "bidirectional"))
    )
    (net (code "94") (name "unconnected-(D1-(SCL{slash}XCK0{slash}OC0AHS{slash}OC0B)PC1-Pad11)") (class "Default")
      (node (ref "D1") (pin "11") (pinfunction "(SCL/XCK0/OC0AHS/OC0B)PC1_11") (pintype "bidirectional"))
    )
    (net (code "95") (name "unconnected-(D1-(SDA{slash}OC0A)PE0-Pad28)") (class "Default")
      (node (ref "D1") (pin "28") (pinfunction "(SDA/OC0A)PE0_28") (pintype "bidirectional"))
    )
    (net (code "96") (name "unconnected-(D1-(SDA{slash}OC0ALS{slash}OC0A)PC0-Pad10)") (class "Default")
      (node (ref "D1") (pin "10") (pinfunction "(SDA/OC0ALS/OC0A)PC0_10") (pintype "bidirectional"))
    )
    (net (code "97") (name "unconnected-(D1-(TXD0{slash}OC0BHS{slash}OC0D)PC3-Pad13)") (class "Default")
      (node (ref "D1") (pin "13") (pinfunction "(TXD0/OC0BHS/OC0D)PC3_13") (pintype "bidirectional"))
    )
    (net (code "98") (name "unconnected-(D1-(~{SS}{slash}OC1A{slash}OC0CLS)PC4-Pad14)") (class "Default")
      (node (ref "D1") (pin "14") (pinfunction "(~{SS}/OC1A/OC0CLS)PC4_14") (pintype "bidirectional"))
    )
    (net (code "99") (name "unconnected-(IC1A-SER-Pad10)") (class "Default")
      (node (ref "IC1") (pin "10") (pinfunction "SER_10") (pintype "input"))
    )
    (net (code "100") (name "unconnected-(IC1A-~{QH}-Pad7)") (class "Default")
      (node (ref "IC1") (pin "7") (pinfunction "~{QH}_7") (pintype "output"))
    )
    (net (code "101") (name "unconnected-(IC2A-~{QH}-Pad7)") (class "Default")
      (node (ref "IC2") (pin "7") (pinfunction "~{QH}_7") (pintype "output"))
    )
    (net (code "102") (name "unconnected-(JP1-Pad3)") (class "Default")
      (node (ref "JP1") (pin "3") (pinfunction "3_3") (pintype "passive"))
    )
    (net (code "103") (name "unconnected-(XW1-MOSI-Pad4)") (class "Default")
      (node (ref "XW1") (pin "4") (pinfunction "MOSI_4") (pintype "bidirectional"))
    )
    (net (code "104") (name "unconnected-(XW1-SCK-Pad3)") (class "Default")
      (node (ref "XW1") (pin "3") (pinfunction "SCK_3") (pintype "bidirectional"))
    )
  )
)
